# SquarePS.net
KiCad netlist of a schematic drawn in Altium Designer
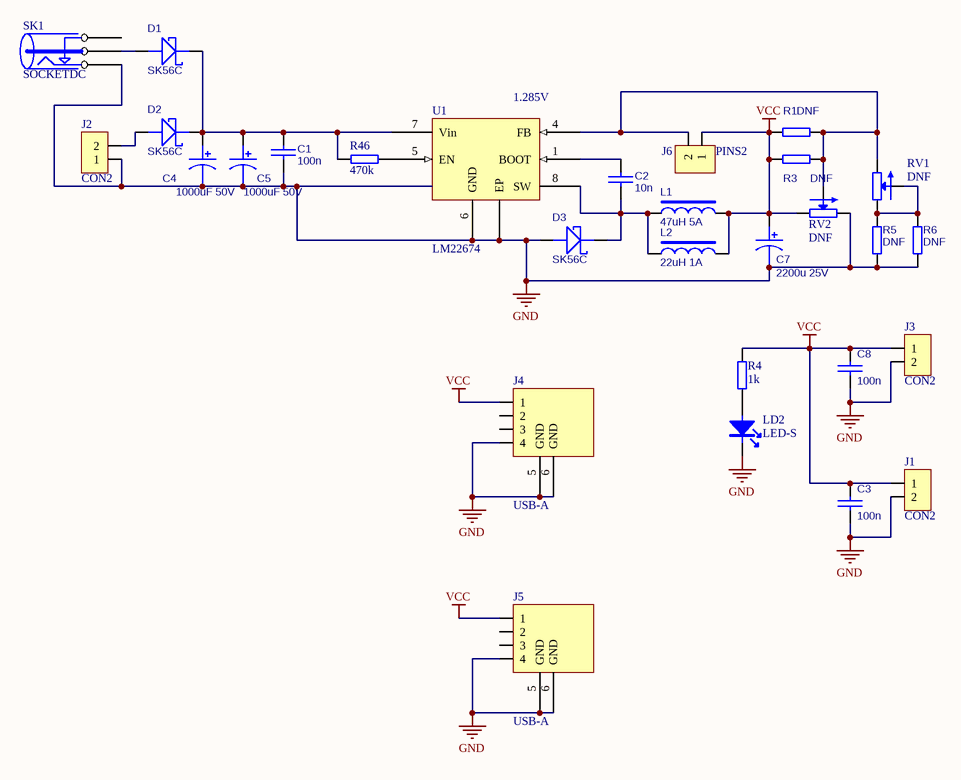
[diagram p0: SquarePS.SchDoc]

(export (version "E")
  (design (tool "Eeschema 10.0.6"))
  (components
    (comp (ref "C1") (value "100n") (footprint "0603") (libsource (lib "*") (part "CAP")))
    (comp (ref "C2") (value "10n") (footprint "0603") (libsource (lib "*") (part "CAP")))
    (comp (ref "C3") (value "100n") (footprint "0603") (libsource (lib "*") (part "CAP")))
    (comp (ref "C4") (value "1000uF 50V") (footprint "RB.3/.7") (libsource (lib "*") (part "CAPACITOR POL")))
    (comp (ref "C5") (value "1000uF 50V") (footprint "RB.3/.7") (libsource (lib "*") (part "CAPACITOR POL")))
    (comp (ref "C7")
      (value "2200u 25V")
      (footprint "RB.2/.5")
      (libsource (lib "DEVICE") (part "CAPACITOR POL"))
    )
    (comp (ref "C8") (value "100n") (footprint "0603") (libsource (lib "*") (part "CAP")))
    (comp (ref "D1") (value "SK56C") (footprint "SMC") (libsource (lib "DEVICE") (part "DIODE SCHOTTKY")))
    (comp (ref "D2") (value "SK56C") (footprint "SMC") (libsource (lib "DEVICE") (part "DIODE SCHOTTKY")))
    (comp (ref "D3") (value "SK56C") (footprint "SMC") (libsource (lib "DEVICE") (part "DIODE SCHOTTKY")))
    (comp (ref "J1") (value "CON2") (footprint "Terms5mm2") (libsource (lib "") (part "CON2_2")))
    (comp (ref "J2") (value "CON2") (footprint "Terms5mm2") (libsource (lib "DEVICE") (part "CON2")))
    (comp (ref "J3") (value "CON2") (footprint "Terms5mm2") (libsource (lib "") (part "CON2_2")))
    (comp (ref "J4") (value "USB-A") (footprint "USB_A") (libsource (lib "DEVICE") (part "USB-A")))
    (comp (ref "J5") (value "USB-A") (footprint "USB_A") (libsource (lib "DEVICE") (part "USB-A")))
    (comp (ref "J6") (value "PINS2") (footprint "SIP2") (libsource (lib "") (part "CON2_1")))
    (comp (ref "L1") (value "47uH 5A") (footprint "Inductor370x930") (libsource (lib "*") (part "INDUCTOR2")))
    (comp (ref "L2") (value "22uH 1A") (footprint "INDUCTOR6B") (libsource (lib "") (part "INDUCTOR2_1")))
    (comp (ref "LD2")
      (value "LED-S")
      (footprint "0805Diode")
      (description "LED")
      (libsource (lib "DEVICE") (part "LED-S"))
    )
    (comp (ref "R1") (value "DNF") (footprint "0603") (libsource (lib "*") (part "RES8")))
    (comp (ref "R3") (value "DNF") (footprint "0603") (libsource (lib "*") (part "RES8")))
    (comp (ref "R4") (value "1k") (footprint "0603") (libsource (lib "DEVICE") (part "RES8")))
    (comp (ref "R5") (value "DNF") (footprint "0603") (libsource (lib "*") (part "RES8")))
    (comp (ref "R6") (value "DNF") (footprint "0603") (libsource (lib "*") (part "RES8")))
    (comp (ref "R46") (value "470k") (footprint "0603") (libsource (lib "DEVICE") (part "RES8")))
    (comp (ref "RV1") (value "DNF") (footprint "VR3362P") (libsource (lib "DEVICE") (part "RES6")))
    (comp (ref "RV2") (value "DNF") (footprint "VR3362P") (libsource (lib "DEVICE") (part "RES6")))
    (comp (ref "SK1")
      (value "SOCKETDC")
      (footprint "SKTPWR")
      (description "DC Power Connector")
      (libsource (lib "*") (part "SOCKETDC"))
    )
    (comp (ref "U1")
      (value "LM22674")
      (footprint "PSOP-8")
      (description "1A SMPS")
      (libsource (lib "NS-EXTRA") (part "LM22675"))
    )
  )
  (nets
    (net (code "1") (name "GND") (class "Default")
      (node (ref "C1") (pin "1") (pintype "passive"))
      (node (ref "C3") (pin "2") (pintype "passive"))
      (node (ref "C4") (pin "2") (pinfunction "2_2") (pintype "passive"))
      (node (ref "C5") (pin "2") (pinfunction "2_2") (pintype "passive"))
      (node (ref "C7") (pin "2") (pinfunction "2_2") (pintype "passive"))
      (node (ref "C8") (pin "2") (pintype "passive"))
      (node (ref "D3") (pin "A") (pinfunction "A_A") (pintype "passive"))
      (node (ref "J1") (pin "2") (pinfunction "2_2") (pintype "passive"))
      (node (ref "J2") (pin "1") (pinfunction "1_1") (pintype "passive"))
      (node (ref "J3") (pin "2") (pinfunction "2_2") (pintype "passive"))
      (node (ref "J4") (pin "4") (pinfunction "4_4") (pintype "passive"))
      (node (ref "J4") (pin "5") (pinfunction "GND_5") (pintype "power_in"))
      (node (ref "J4") (pin "6") (pinfunction "GND_6") (pintype "power_in"))
      (node (ref "J5") (pin "4") (pinfunction "4_4") (pintype "passive"))
      (node (ref "J5") (pin "5") (pinfunction "GND_5") (pintype "power_in"))
      (node (ref "J5") (pin "6") (pinfunction "GND_6") (pintype "power_in"))
      (node (ref "LD2") (pin "K") (pintype "passive"))
      (node (ref "R5") (pin "1") (pintype "passive"))
      (node (ref "R6") (pin "1") (pintype "passive"))
      (node (ref "RV2") (pin "CW") (pinfunction "CW_CW") (pintype "passive"))
      (node (ref "SK1") (pin "COM") (pinfunction "COM_COM") (pintype "passive"))
      (node (ref "U1") (pin "6") (pinfunction "GND_6") (pintype "power_in"))
      (node (ref "U1") (pin "9") (pinfunction "EP_9") (pintype "power_in"))
    )
    (net (code "2") (name "Net-(D1-PadA)") (class "Default")
      (node (ref "D1") (pin "A") (pinfunction "A_A") (pintype "passive"))
      (node (ref "SK1") (pin "PIN") (pinfunction "PIN_PIN") (pintype "passive"))
    )
    (net (code "3") (name "Net-(D2-PadA)") (class "Default")
      (node (ref "D2") (pin "A") (pinfunction "A_A") (pintype "passive"))
      (node (ref "J2") (pin "2") (pinfunction "2_2") (pintype "passive"))
    )
    (net (code "4") (name "Net-(LD2-PadA)") (class "Default")
      (node (ref "LD2") (pin "A") (pintype "passive"))
      (node (ref "R4") (pin "2") (pintype "passive"))
    )
    (net (code "5") (name "Net-(R5-Pad2)") (class "Default")
      (node (ref "R5") (pin "2") (pintype "passive"))
      (node (ref "R6") (pin "2") (pintype "passive"))
      (node (ref "RV1") (pin "CCW") (pinfunction "CCW_CCW") (pintype "passive"))
      (node (ref "RV1") (pin "W") (pinfunction "W_W") (pintype "passive"))
    )
    (net (code "6") (name "Net-(U1-BOOT)") (class "Default")
      (node (ref "C2") (pin "1") (pintype "passive"))
      (node (ref "U1") (pin "1") (pinfunction "BOOT_1") (pintype "input"))
    )
    (net (code "7") (name "Net-(U1-EN)") (class "Default")
      (node (ref "R46") (pin "1") (pintype "passive"))
      (node (ref "U1") (pin "5") (pinfunction "EN_5") (pintype "input"))
    )
    (net (code "8") (name "Net-(U1-FB)") (class "Default")
      (node (ref "J6") (pin "2") (pinfunction "2_2") (pintype "passive"))
      (node (ref "R1") (pin "1") (pintype "passive"))
      (node (ref "R3") (pin "1") (pintype "passive"))
      (node (ref "RV1") (pin "CW") (pinfunction "CW_CW") (pintype "passive"))
      (node (ref "RV2") (pin "W") (pinfunction "W_W") (pintype "passive"))
      (node (ref "U1") (pin "4") (pinfunction "FB_4") (pintype "input"))
    )
    (net (code "9") (name "Net-(U1-SW)") (class "Default")
      (node (ref "C2") (pin "2") (pintype "passive"))
      (node (ref "D3") (pin "K") (pinfunction "K_K") (pintype "passive"))
      (node (ref "L1") (pin "2") (pintype "passive"))
      (node (ref "L2") (pin "1") (pintype "passive"))
      (node (ref "U1") (pin "8") (pinfunction "SW_8") (pintype "power_in"))
    )
    (net (code "10") (name "Net-(U1-Vin)") (class "Default")
      (node (ref "C1") (pin "2") (pintype "passive"))
      (node (ref "C4") (pin "1") (pinfunction "1_1") (pintype "passive"))
      (node (ref "C5") (pin "1") (pinfunction "1_1") (pintype "passive"))
      (node (ref "D1") (pin "K") (pinfunction "K_K") (pintype "passive"))
      (node (ref "D2") (pin "K") (pinfunction "K_K") (pintype "passive"))
      (node (ref "R46") (pin "2") (pintype "passive"))
      (node (ref "U1") (pin "7") (pinfunction "Vin_7") (pintype "passive"))
    )
    (net (code "11") (name "VCC") (class "Default")
      (node (ref "C3") (pin "1") (pintype "passive"))
      (node (ref "C7") (pin "1") (pinfunction "1_1") (pintype "passive"))
      (node (ref "C8") (pin "1") (pintype "passive"))
      (node (ref "J1") (pin "1") (pinfunction "1_1") (pintype "passive"))
      (node (ref "J3") (pin "1") (pinfunction "1_1") (pintype "passive"))
      (node (ref "J4") (pin "1") (pinfunction "1_1") (pintype "passive"))
      (node (ref "J5") (pin "1") (pinfunction "1_1") (pintype "passive"))
      (node (ref "J6") (pin "1") (pinfunction "1_1") (pintype "passive"))
      (node (ref "L1") (pin "1") (pintype "passive"))
      (node (ref "L2") (pin "2") (pintype "passive"))
      (node (ref "R1") (pin "2") (pintype "passive"))
      (node (ref "R3") (pin "2") (pintype "passive"))
      (node (ref "R4") (pin "1") (pintype "passive"))
      (node (ref "RV2") (pin "CCW") (pinfunction "CCW_CCW") (pintype "passive"))
    )
    (net (code "12") (name "unconnected-(J4-Pad2)") (class "Default")
      (node (ref "J4") (pin "2") (pinfunction "2_2") (pintype "passive"))
    )
    (net (code "13") (name "unconnected-(J4-Pad3)") (class "Default")
      (node (ref "J4") (pin "3") (pinfunction "3_3") (pintype "passive"))
    )
    (net (code "14") (name "unconnected-(J5-Pad2)") (class "Default")
      (node (ref "J5") (pin "2") (pinfunction "2_2") (pintype "passive"))
    )
    (net (code "15") (name "unconnected-(J5-Pad3)") (class "Default")
      (node (ref "J5") (pin "3") (pinfunction "3_3") (pintype "passive"))
    )
    (net (code "16") (name "unconnected-(SK1-PadSW)") (class "Default")
      (node (ref "SK1") (pin "SW") (pinfunction "SW_SW") (pintype "passive"))
    )
  )
)
